# femtoduinoUSB.net
KiCad netlist of a schematic drawn in EAGLE
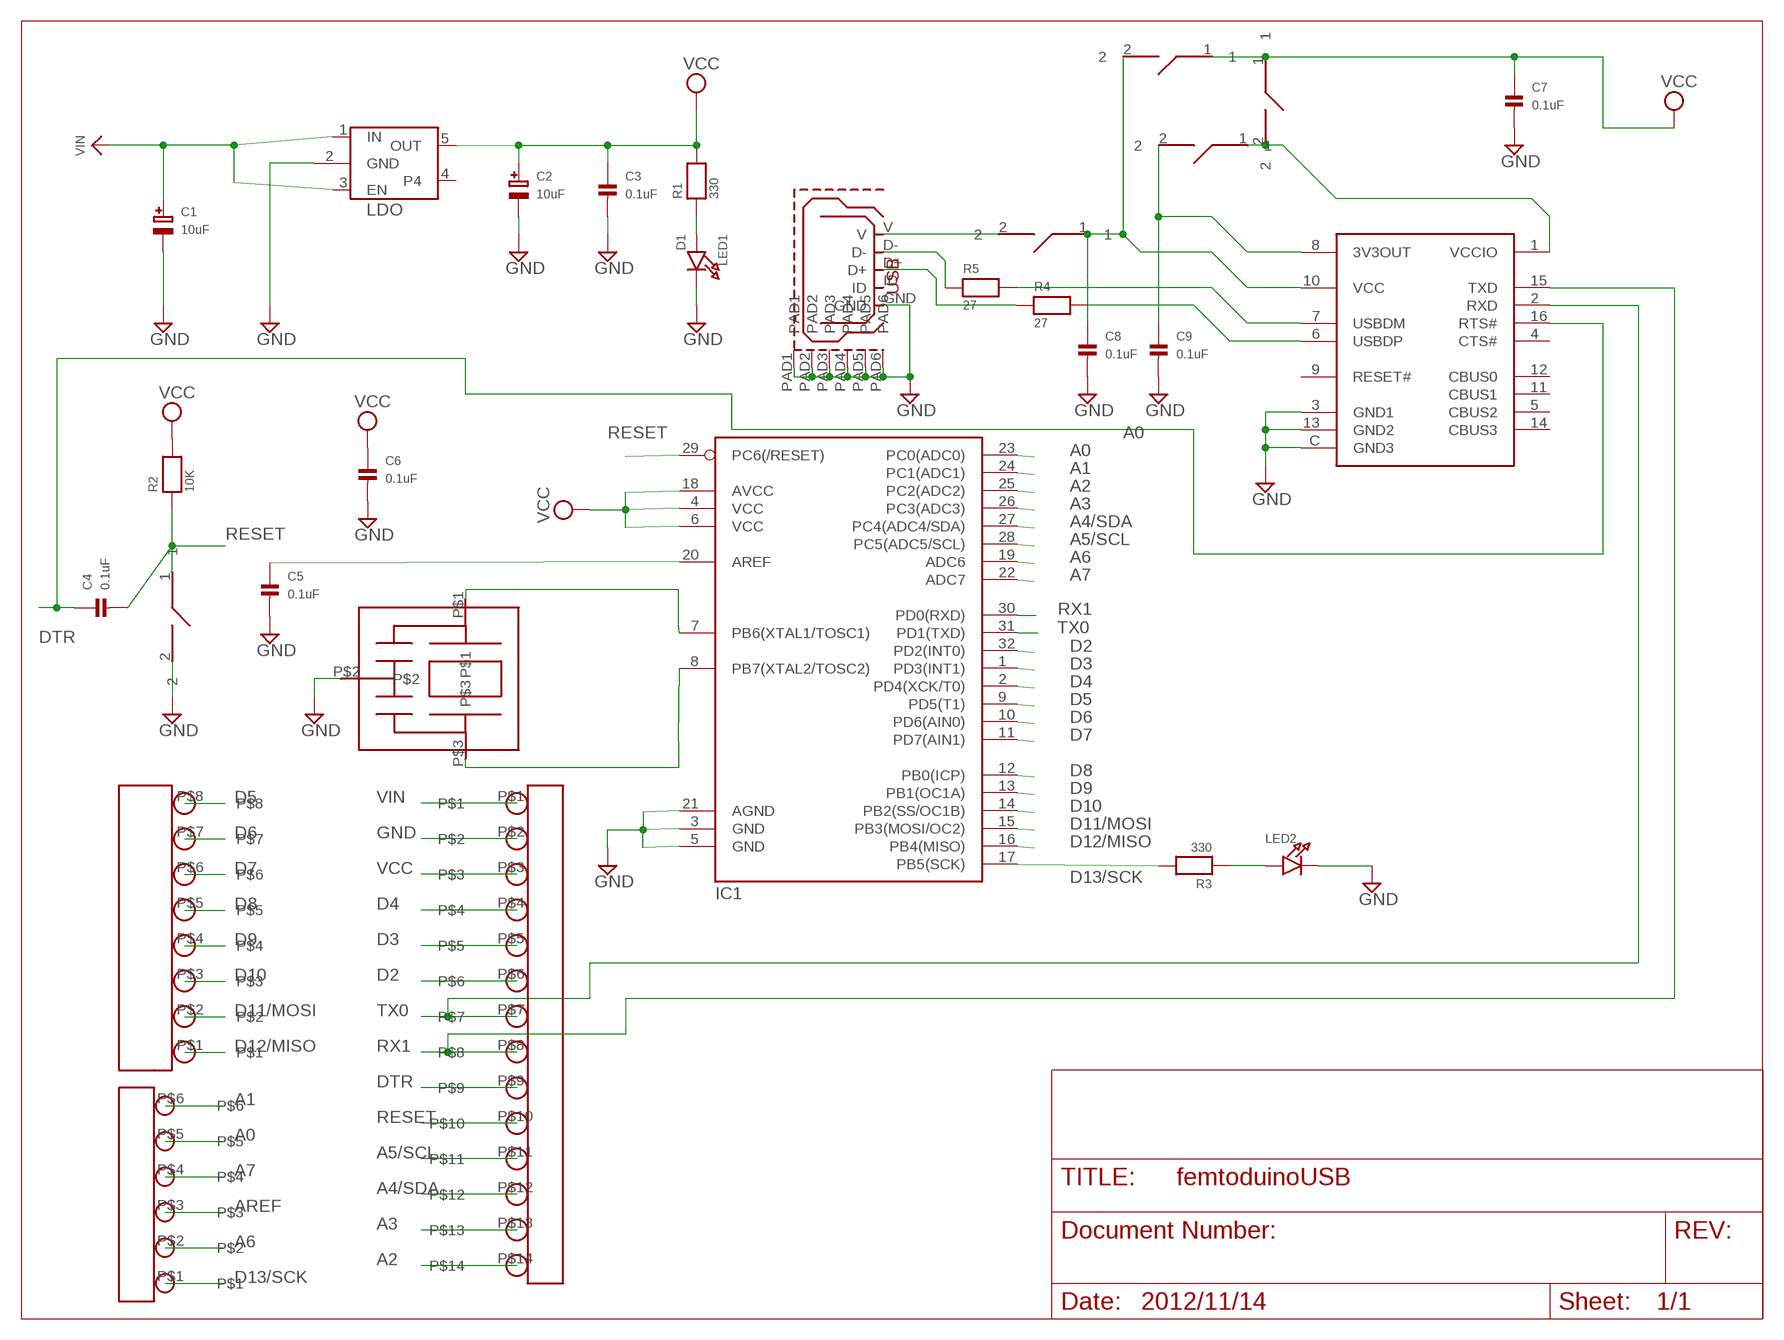
[diagram p0: schematic, sheet 1]

(export (version "E")
  (design (tool "Eeschema 10.0.6"))
  (components
    (comp (ref "C1")
      (value "10uF")
      (footprint "eagle-import:EIA3528-21_B-W")
      (libsource (lib "eagle-import") (part "CAP_TANTALUMB/3528_WAVE"))
    )
    (comp (ref "C2")
      (value "10uF")
      (footprint "eagle-import:EIA3528-21_B-W")
      (libsource (lib "eagle-import") (part "CAP_TANTALUMB/3528_WAVE"))
    )
    (comp (ref "C3")
      (value "0.1uF")
      (footprint "eagle-import:0402")
      (libsource (lib "eagle-import") (part "CAP_CERAMIC0402"))
    )
    (comp (ref "C4")
      (value "0.1uF")
      (footprint "eagle-import:0402")
      (libsource (lib "eagle-import") (part "CAP_CERAMIC0402"))
    )
    (comp (ref "C5")
      (value "0.1uF")
      (footprint "eagle-import:0402")
      (libsource (lib "eagle-import") (part "CAP_CERAMIC0402"))
    )
    (comp (ref "C6")
      (value "0.1uF")
      (footprint "eagle-import:0402")
      (libsource (lib "eagle-import") (part "CAP_CERAMIC0402"))
    )
    (comp (ref "C7")
      (value "0.1uF")
      (footprint "eagle-import:0402")
      (libsource (lib "eagle-import") (part "CAP_CERAMIC0402"))
    )
    (comp (ref "C8")
      (value "0.1uF")
      (footprint "eagle-import:0402")
      (libsource (lib "eagle-import") (part "CAP_CERAMIC0402"))
    )
    (comp (ref "C9")
      (value "0.1uF")
      (footprint "eagle-import:0402")
      (libsource (lib "eagle-import") (part "CAP_CERAMIC0402"))
    )
    (comp (ref "IC1")
      (value "ATMEGA168MLF")
      (footprint "eagle-import:MLF32")
      (libsource (lib "eagle-import") (part "ATMEGA168MLF"))
    )
    (comp (ref "LED1")
      (value "D1")
      (footprint "eagle-import:CHIPLED_0805")
      (libsource (lib "eagle-import") (part "LED0805"))
    )
    (comp (ref "LED2")
      (value "LED0805")
      (footprint "eagle-import:CHIPLED_0805")
      (libsource (lib "eagle-import") (part "LED0805"))
    )
    (comp (ref "R1")
      (value "330")
      (footprint "eagle-import:0402")
      (libsource (lib "eagle-import") (part "RESISTOR0402"))
    )
    (comp (ref "R2")
      (value "10K")
      (footprint "eagle-import:0402")
      (libsource (lib "eagle-import") (part "RESISTOR0402"))
    )
    (comp (ref "R3")
      (value "330")
      (footprint "eagle-import:0402")
      (libsource (lib "eagle-import") (part "RESISTOR0402"))
    )
    (comp (ref "R4")
      (value "27")
      (footprint "eagle-import:0402")
      (libsource (lib "eagle-import") (part "RESISTOR0402"))
    )
    (comp (ref "R5")
      (value "27")
      (footprint "eagle-import:0402")
      (libsource (lib "eagle-import") (part "RESISTOR0402"))
    )
    (comp (ref "SJ1")
      (value "SPST_SMD")
      (footprint "eagle-import:SPST_SMD")
      (libsource (lib "eagle-import") (part "SPST_SMD"))
    )
    (comp (ref "SJ2")
      (value "SPST_SMD")
      (footprint "eagle-import:SPST_SMD")
      (libsource (lib "eagle-import") (part "SPST_SMD"))
    )
    (comp (ref "SJ3")
      (value "SPST_SMD")
      (footprint "eagle-import:SPST_SMD")
      (libsource (lib "eagle-import") (part "SPST_SMD"))
    )
    (comp (ref "SJ4")
      (value "SPST_SMD")
      (footprint "eagle-import:SPST_SMD")
      (libsource (lib "eagle-import") (part "SPST_SMD"))
    )
    (comp (ref "U$2")
      (value "05_PINHEAD_1X6")
      (footprint "eagle-import:05_PINHEAD_1X6_PACKAGE")
      (libsource (lib "eagle-import") (part "05_PINHEAD_1X6"))
    )
    (comp (ref "U$3")
      (value "05_PINHEAD_1X8")
      (footprint "eagle-import:05_PINHEAD_1X8_PACKAGE")
      (libsource (lib "eagle-import") (part "05_PINHEAD_1X8"))
    )
    (comp (ref "U$4")
      (value "05_PINHEAD_1X14")
      (footprint "eagle-import:05_PINHEAD_1X14_PACKAGE")
      (libsource (lib "eagle-import") (part "05_PINHEAD_1X14"))
    )
    (comp (ref "U$5")
      (value "CSTCE16MOV51-RO")
      (footprint "eagle-import:CSTCE16M0V51-RO_PACKAGE")
      (libsource (lib "eagle-import") (part "CSTCE16MOV51-RO"))
    )
    (comp (ref "U$6")
      (value "SPST_SMD")
      (footprint "eagle-import:SPST_SMD")
      (libsource (lib "eagle-import") (part "SPST_SMD"))
    )
    (comp (ref "U$7")
      (value "FT230XQ")
      (footprint "eagle-import:FT230XQ")
      (libsource (lib "eagle-import") (part "FT230XQ"))
    )
    (comp (ref "U1")
      (value "MIC5205")
      (footprint "eagle-import:LDO_REGULATOR")
      (libsource (lib "eagle-import") (part "LDO_REGULATOR"))
    )
    (comp (ref "USB1")
      (value "USB_MICROB")
      (footprint "eagle-import:USB_MICROB_PACKAGE")
      (libsource (lib "eagle-import") (part "USB_MICROB"))
    )
  )
  (nets
    (net (code "1") (name "/A0") (class "Default")
      (node (ref "IC1") (pin "23") (pinfunction "PC0(ADC0)_23") (pintype "bidirectional"))
      (node (ref "U$2") (pin "P$5") (pinfunction "P$5_P$5") (pintype "bidirectional"))
    )
    (net (code "2") (name "/A1") (class "Default")
      (node (ref "IC1") (pin "24") (pinfunction "PC1(ADC1)_24") (pintype "bidirectional"))
      (node (ref "U$2") (pin "P$6") (pinfunction "P$6_P$6") (pintype "bidirectional"))
    )
    (net (code "3") (name "/A2") (class "Default")
      (node (ref "IC1") (pin "25") (pinfunction "PC2(ADC2)_25") (pintype "bidirectional"))
      (node (ref "U$4") (pin "P$14") (pinfunction "P$14_P$14") (pintype "bidirectional"))
    )
    (net (code "4") (name "/A3") (class "Default")
      (node (ref "IC1") (pin "26") (pinfunction "PC3(ADC3)_26") (pintype "bidirectional"))
      (node (ref "U$4") (pin "P$13") (pinfunction "P$13_P$13") (pintype "bidirectional"))
    )
    (net (code "5") (name "/A4{slash}SDA") (class "Default")
      (node (ref "IC1") (pin "27") (pinfunction "PC4(ADC4/SDA)_27") (pintype "bidirectional"))
      (node (ref "U$4") (pin "P$12") (pinfunction "P$12_P$12") (pintype "bidirectional"))
    )
    (net (code "6") (name "/A5{slash}SCL") (class "Default")
      (node (ref "IC1") (pin "28") (pinfunction "PC5(ADC5/SCL)_28") (pintype "bidirectional"))
      (node (ref "U$4") (pin "P$11") (pinfunction "P$11_P$11") (pintype "bidirectional"))
    )
    (net (code "7") (name "/A6") (class "Default")
      (node (ref "IC1") (pin "19") (pinfunction "ADC6_19") (pintype "bidirectional"))
      (node (ref "U$2") (pin "P$2") (pinfunction "P$2_P$2") (pintype "bidirectional"))
    )
    (net (code "8") (name "/A7") (class "Default")
      (node (ref "IC1") (pin "22") (pinfunction "ADC7_22") (pintype "bidirectional"))
      (node (ref "U$2") (pin "P$4") (pinfunction "P$4_P$4") (pintype "bidirectional"))
    )
    (net (code "9") (name "/AREF") (class "Default")
      (node (ref "C5") (pin "1") (pinfunction "P$1_1") (pintype "passive"))
      (node (ref "IC1") (pin "20") (pinfunction "AREF_20") (pintype "bidirectional"))
      (node (ref "U$2") (pin "P$3") (pinfunction "P$3_P$3") (pintype "bidirectional"))
    )
    (net (code "10") (name "/D2") (class "Default")
      (node (ref "IC1") (pin "32") (pinfunction "PD2(INT0)_32") (pintype "bidirectional"))
      (node (ref "U$4") (pin "P$6") (pinfunction "P$6_P$6") (pintype "bidirectional"))
    )
    (net (code "11") (name "/D3") (class "Default")
      (node (ref "IC1") (pin "1") (pinfunction "PD3(INT1)_1") (pintype "bidirectional"))
      (node (ref "U$4") (pin "P$5") (pinfunction "P$5_P$5") (pintype "bidirectional"))
    )
    (net (code "12") (name "/D4") (class "Default")
      (node (ref "IC1") (pin "2") (pinfunction "PD4(XCK/T0)_2") (pintype "bidirectional"))
      (node (ref "U$4") (pin "P$4") (pinfunction "P$4_P$4") (pintype "bidirectional"))
    )
    (net (code "13") (name "/D5") (class "Default")
      (node (ref "IC1") (pin "9") (pinfunction "PD5(T1)_9") (pintype "bidirectional"))
      (node (ref "U$3") (pin "P$8") (pinfunction "P$8_P$8") (pintype "bidirectional"))
    )
    (net (code "14") (name "/D6") (class "Default")
      (node (ref "IC1") (pin "10") (pinfunction "PD6(AIN0)_10") (pintype "bidirectional"))
      (node (ref "U$3") (pin "P$7") (pinfunction "P$7_P$7") (pintype "bidirectional"))
    )
    (net (code "15") (name "/D7") (class "Default")
      (node (ref "IC1") (pin "11") (pinfunction "PD7(AIN1)_11") (pintype "bidirectional"))
      (node (ref "U$3") (pin "P$6") (pinfunction "P$6_P$6") (pintype "bidirectional"))
    )
    (net (code "16") (name "/D8") (class "Default")
      (node (ref "IC1") (pin "12") (pinfunction "PB0(ICP)_12") (pintype "bidirectional"))
      (node (ref "U$3") (pin "P$5") (pinfunction "P$5_P$5") (pintype "bidirectional"))
    )
    (net (code "17") (name "/D9") (class "Default")
      (node (ref "IC1") (pin "13") (pinfunction "PB1(OC1A)_13") (pintype "bidirectional"))
      (node (ref "U$3") (pin "P$4") (pinfunction "P$4_P$4") (pintype "bidirectional"))
    )
    (net (code "18") (name "/D10") (class "Default")
      (node (ref "IC1") (pin "14") (pinfunction "PB2(SS/OC1B)_14") (pintype "bidirectional"))
      (node (ref "U$3") (pin "P$3") (pinfunction "P$3_P$3") (pintype "bidirectional"))
    )
    (net (code "19") (name "/D11{slash}MOSI") (class "Default")
      (node (ref "IC1") (pin "15") (pinfunction "PB3(MOSI/OC2)_15") (pintype "bidirectional"))
      (node (ref "U$3") (pin "P$2") (pinfunction "P$2_P$2") (pintype "bidirectional"))
    )
    (net (code "20") (name "/D12{slash}MISO") (class "Default")
      (node (ref "IC1") (pin "16") (pinfunction "PB4(MISO)_16") (pintype "bidirectional"))
      (node (ref "U$3") (pin "P$1") (pinfunction "P$1_P$1") (pintype "bidirectional"))
    )
    (net (code "21") (name "/D13{slash}SCK") (class "Default")
      (node (ref "IC1") (pin "17") (pinfunction "PB5(SCK)_17") (pintype "bidirectional"))
      (node (ref "R3") (pin "2") (pinfunction "2_2") (pintype "passive"))
      (node (ref "U$2") (pin "P$1") (pinfunction "P$1_P$1") (pintype "bidirectional"))
    )
    (net (code "22") (name "/DTR") (class "Default")
      (node (ref "C4") (pin "1") (pinfunction "P$1_1") (pintype "passive"))
      (node (ref "U$4") (pin "P$9") (pinfunction "P$9_P$9") (pintype "bidirectional"))
      (node (ref "U$7") (pin "16") (pinfunction "RTS#_16") (pintype "bidirectional"))
    )
    (net (code "23") (name "/RESET") (class "Default")
      (node (ref "C4") (pin "2") (pinfunction "P$2_2") (pintype "passive"))
      (node (ref "IC1") (pin "29") (pinfunction "PC6(/RESET)_29") (pintype "bidirectional"))
      (node (ref "R2") (pin "1") (pinfunction "1_1") (pintype "passive"))
      (node (ref "U$4") (pin "P$10") (pinfunction "P$10_P$10") (pintype "bidirectional"))
      (node (ref "U$6") (pin "1") (pinfunction "1_1") (pintype "bidirectional"))
    )
    (net (code "24") (name "/RX1") (class "Default")
      (node (ref "IC1") (pin "30") (pinfunction "PD0(RXD)_30") (pintype "bidirectional"))
      (node (ref "U$4") (pin "P$8") (pinfunction "P$8_P$8") (pintype "bidirectional"))
      (node (ref "U$7") (pin "15") (pinfunction "TXD_15") (pintype "bidirectional"))
    )
    (net (code "25") (name "/TX0") (class "Default")
      (node (ref "IC1") (pin "31") (pinfunction "PD1(TXD)_31") (pintype "bidirectional"))
      (node (ref "U$4") (pin "P$7") (pinfunction "P$7_P$7") (pintype "bidirectional"))
      (node (ref "U$7") (pin "2") (pinfunction "RXD_2") (pintype "bidirectional"))
    )
    (net (code "26") (name "GND") (class "Default")
      (node (ref "C1") (pin "-") (pinfunction "-_-") (pintype "passive"))
      (node (ref "C2") (pin "-") (pinfunction "-_-") (pintype "passive"))
      (node (ref "C3") (pin "2") (pinfunction "P$2_2") (pintype "passive"))
      (node (ref "C5") (pin "2") (pinfunction "P$2_2") (pintype "passive"))
      (node (ref "C6") (pin "2") (pinfunction "P$2_2") (pintype "passive"))
      (node (ref "C7") (pin "2") (pinfunction "P$2_2") (pintype "passive"))
      (node (ref "C8") (pin "2") (pinfunction "P$2_2") (pintype "passive"))
      (node (ref "C9") (pin "2") (pinfunction "P$2_2") (pintype "passive"))
      (node (ref "IC1") (pin "21") (pinfunction "AGND_21") (pintype "bidirectional"))
      (node (ref "IC1") (pin "3") (pinfunction "GND_3") (pintype "bidirectional"))
      (node (ref "IC1") (pin "5") (pinfunction "GND_5") (pintype "bidirectional"))
      (node (ref "LED1") (pin "C") (pinfunction "C_C") (pintype "passive"))
      (node (ref "LED2") (pin "C") (pinfunction "C_C") (pintype "passive"))
      (node (ref "U$4") (pin "P$2") (pinfunction "P$2_P$2") (pintype "bidirectional"))
      (node (ref "U$5") (pin "P$2") (pinfunction "P$2_P$2") (pintype "bidirectional"))
      (node (ref "U$6") (pin "2") (pinfunction "2_2") (pintype "bidirectional"))
      (node (ref "U$7") (pin "13") (pinfunction "GND2_13") (pintype "bidirectional"))
      (node (ref "U$7") (pin "3") (pinfunction "GND1_3") (pintype "bidirectional"))
      (node (ref "U$7") (pin "C") (pinfunction "GND3_C") (pintype "bidirectional"))
      (node (ref "U1") (pin "2") (pinfunction "GND_2") (pintype "bidirectional"))
      (node (ref "USB1") (pin "GND") (pinfunction "GND_GND") (pintype "bidirectional"))
      (node (ref "USB1") (pin "PAD1") (pinfunction "PAD1_PAD1") (pintype "bidirectional"))
      (node (ref "USB1") (pin "PAD2") (pinfunction "PAD2_PAD2") (pintype "bidirectional"))
      (node (ref "USB1") (pin "PAD3") (pinfunction "PAD3_PAD3") (pintype "bidirectional"))
      (node (ref "USB1") (pin "PAD4") (pinfunction "PAD4_PAD4") (pintype "bidirectional"))
      (node (ref "USB1") (pin "PAD5") (pinfunction "PAD5_PAD5") (pintype "bidirectional"))
      (node (ref "USB1") (pin "PAD6") (pinfunction "PAD6_PAD6") (pintype "bidirectional"))
    )
    (net (code "27") (name "Net-(C8-P$1)") (class "Default")
      (node (ref "C8") (pin "1") (pinfunction "P$1_1") (pintype "passive"))
      (node (ref "SJ1") (pin "1") (pinfunction "1_1") (pintype "bidirectional"))
      (node (ref "SJ2") (pin "2") (pinfunction "2_2") (pintype "bidirectional"))
      (node (ref "U$7") (pin "10") (pinfunction "VCC_10") (pintype "bidirectional"))
    )
    (net (code "28") (name "Net-(C9-P$1)") (class "Default")
      (node (ref "C9") (pin "1") (pinfunction "P$1_1") (pintype "passive"))
      (node (ref "SJ4") (pin "2") (pinfunction "2_2") (pintype "bidirectional"))
      (node (ref "U$7") (pin "8") (pinfunction "3V3OUT_8") (pintype "bidirectional"))
    )
    (net (code "29") (name "Net-(IC1-PB6(XTAL1{slash}TOSC1))") (class "Default")
      (node (ref "IC1") (pin "7") (pinfunction "PB6(XTAL1/TOSC1)_7") (pintype "bidirectional"))
      (node (ref "U$5") (pin "P$1") (pinfunction "P$1_P$1") (pintype "bidirectional"))
    )
    (net (code "30") (name "Net-(IC1-PB7(XTAL2{slash}TOSC2))") (class "Default")
      (node (ref "IC1") (pin "8") (pinfunction "PB7(XTAL2/TOSC2)_8") (pintype "bidirectional"))
      (node (ref "U$5") (pin "P$3") (pinfunction "P$3_P$3") (pintype "bidirectional"))
    )
    (net (code "31") (name "Net-(LED1-PadA)") (class "Default")
      (node (ref "LED1") (pin "A") (pinfunction "A_A") (pintype "passive"))
      (node (ref "R1") (pin "1") (pinfunction "1_1") (pintype "passive"))
    )
    (net (code "32") (name "Net-(LED2-PadA)") (class "Default")
      (node (ref "LED2") (pin "A") (pinfunction "A_A") (pintype "passive"))
      (node (ref "R3") (pin "1") (pinfunction "1_1") (pintype "passive"))
    )
    (net (code "33") (name "Net-(R4-Pad1)") (class "Default")
      (node (ref "R4") (pin "1") (pinfunction "1_1") (pintype "passive"))
      (node (ref "USB1") (pin "D+") (pinfunction "D+_D+") (pintype "bidirectional"))
    )
    (net (code "34") (name "Net-(R5-Pad1)") (class "Default")
      (node (ref "R5") (pin "1") (pinfunction "1_1") (pintype "passive"))
      (node (ref "USB1") (pin "D-") (pinfunction "D-_D-") (pintype "bidirectional"))
    )
    (net (code "35") (name "Net-(U$7-USBDM)") (class "Default")
      (node (ref "R5") (pin "2") (pinfunction "2_2") (pintype "passive"))
      (node (ref "U$7") (pin "7") (pinfunction "USBDM_7") (pintype "bidirectional"))
    )
    (net (code "36") (name "Net-(U$7-USBDP)") (class "Default")
      (node (ref "R4") (pin "2") (pinfunction "2_2") (pintype "passive"))
      (node (ref "U$7") (pin "6") (pinfunction "USBDP_6") (pintype "bidirectional"))
    )
    (net (code "37") (name "Net-(U$7-VCCIO)") (class "Default")
      (node (ref "SJ3") (pin "2") (pinfunction "2_2") (pintype "bidirectional"))
      (node (ref "SJ4") (pin "1") (pinfunction "1_1") (pintype "bidirectional"))
      (node (ref "U$7") (pin "1") (pinfunction "VCCIO_1") (pintype "bidirectional"))
    )
    (net (code "38") (name "VCC") (class "Default")
      (node (ref "C2") (pin "+") (pinfunction "+_+") (pintype "passive"))
      (node (ref "C3") (pin "1") (pinfunction "P$1_1") (pintype "passive"))
      (node (ref "C6") (pin "1") (pinfunction "P$1_1") (pintype "passive"))
      (node (ref "C7") (pin "1") (pinfunction "P$1_1") (pintype "passive"))
      (node (ref "IC1") (pin "18") (pinfunction "AVCC_18") (pintype "bidirectional"))
      (node (ref "IC1") (pin "4") (pinfunction "VCC_4") (pintype "bidirectional"))
      (node (ref "IC1") (pin "6") (pinfunction "VCC_6") (pintype "bidirectional"))
      (node (ref "R1") (pin "2") (pinfunction "2_2") (pintype "passive"))
      (node (ref "R2") (pin "2") (pinfunction "2_2") (pintype "passive"))
      (node (ref "SJ1") (pin "2") (pinfunction "2_2") (pintype "bidirectional"))
      (node (ref "SJ2") (pin "1") (pinfunction "1_1") (pintype "bidirectional"))
      (node (ref "SJ3") (pin "1") (pinfunction "1_1") (pintype "bidirectional"))
      (node (ref "U$4") (pin "P$3") (pinfunction "P$3_P$3") (pintype "bidirectional"))
      (node (ref "U1") (pin "5") (pinfunction "OUT_5") (pintype "bidirectional"))
      (node (ref "USB1") (pin "V") (pinfunction "V_V") (pintype "bidirectional"))
    )
    (net (code "39") (name "VIN") (class "Default")
      (node (ref "C1") (pin "+") (pinfunction "+_+") (pintype "passive"))
      (node (ref "U$4") (pin "P$1") (pinfunction "P$1_P$1") (pintype "bidirectional"))
      (node (ref "U1") (pin "1") (pinfunction "IN_1") (pintype "bidirectional"))
      (node (ref "U1") (pin "3") (pinfunction "EN_3") (pintype "bidirectional"))
    )
    (net (code "40") (name "unconnected-(U$7-CBUS0-Pad12)") (class "Default")
      (node (ref "U$7") (pin "12") (pinfunction "CBUS0_12") (pintype "bidirectional"))
    )
    (net (code "41") (name "unconnected-(U$7-CBUS1-Pad11)") (class "Default")
      (node (ref "U$7") (pin "11") (pinfunction "CBUS1_11") (pintype "bidirectional"))
    )
    (net (code "42") (name "unconnected-(U$7-CBUS2-Pad5)") (class "Default")
      (node (ref "U$7") (pin "5") (pinfunction "CBUS2_5") (pintype "bidirectional"))
    )
    (net (code "43") (name "unconnected-(U$7-CBUS3-Pad14)") (class "Default")
      (node (ref "U$7") (pin "14") (pinfunction "CBUS3_14") (pintype "bidirectional"))
    )
    (net (code "44") (name "unconnected-(U$7-CTS#-Pad4)") (class "Default")
      (node (ref "U$7") (pin "4") (pinfunction "CTS#_4") (pintype "bidirectional"))
    )
    (net (code "45") (name "unconnected-(U$7-RESET#-Pad9)") (class "Default")
      (node (ref "U$7") (pin "9") (pinfunction "RESET#_9") (pintype "bidirectional"))
    )
    (net (code "46") (name "unconnected-(U1-P4-Pad4)") (class "Default")
      (node (ref "U1") (pin "4") (pinfunction "P4_4") (pintype "bidirectional"))
    )
    (net (code "47") (name "unconnected-(USB1-PadID)") (class "Default")
      (node (ref "USB1") (pin "ID") (pinfunction "ID_ID") (pintype "bidirectional"))
    )
  )
)
